# MAXREFDES98_Schematic.net
KiCad netlist of a schematic drawn in EAGLE
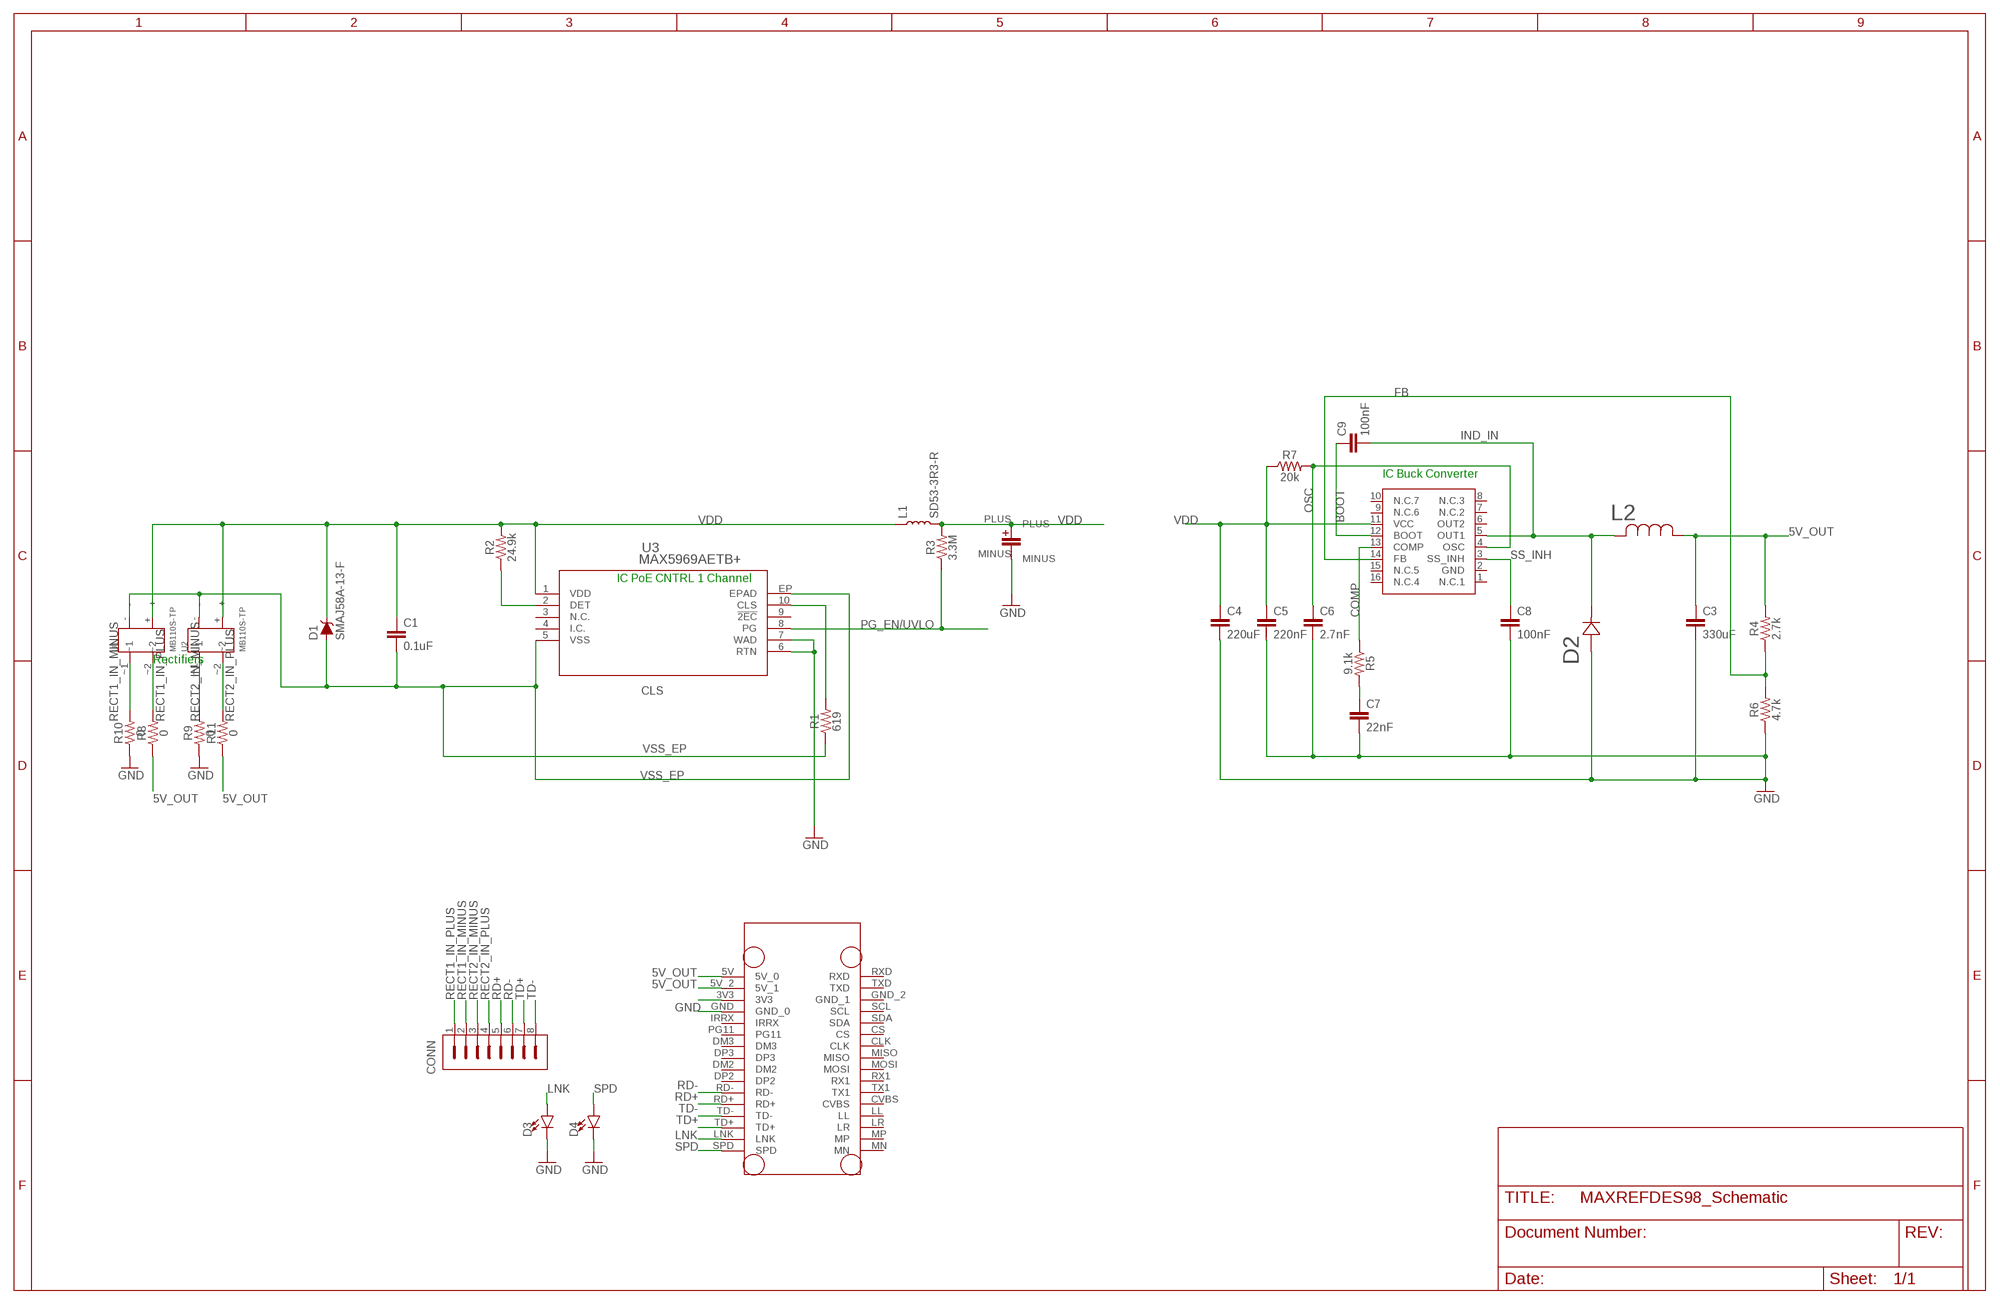
[diagram p0: schematic, sheet 1]

(export (version "E")
  (design (tool "Eeschema 10.0.6"))
  (components
    (comp (ref "C1")
      (value "0.1uF")
      (footprint "eagle-import:0805")
      (libsource (lib "eagle-import") (part "1.0UF-0805-25V-(+80/-20%)"))
    )
    (comp (ref "C2")
      (value "EEE-1JA220UP")
      (footprint "eagle-import:EEE-1JA220UP")
      (libsource (lib "eagle-import") (part "EEE-1JA220UP"))
    )
    (comp (ref "C3")
      (value "330uF")
      (footprint "eagle-import:0603")
      (libsource (lib "eagle-import") (part "4.7UF0603"))
    )
    (comp (ref "C4")
      (value "220uF")
      (footprint "eagle-import:0603")
      (libsource (lib "eagle-import") (part "4.7UF0603"))
    )
    (comp (ref "C5")
      (value "220nF")
      (footprint "eagle-import:0603")
      (libsource (lib "eagle-import") (part "4.7UF0603"))
    )
    (comp (ref "C6")
      (value "2.7nF")
      (footprint "eagle-import:0603")
      (libsource (lib "eagle-import") (part "4.7UF0603"))
    )
    (comp (ref "C7")
      (value "22nF")
      (footprint "eagle-import:0603")
      (libsource (lib "eagle-import") (part "4.7UF0603"))
    )
    (comp (ref "C8")
      (value "100nF")
      (footprint "eagle-import:0603")
      (libsource (lib "eagle-import") (part "4.7UF0603"))
    )
    (comp (ref "C9")
      (value "100nF")
      (footprint "eagle-import:0603")
      (libsource (lib "eagle-import") (part "4.7UF0603"))
    )
    (comp (ref "CONN")
      (value "TERM_BLOCK_PLUG_8POS_STR_2.5MM")
      (footprint "eagle-import:TERM_BLOCK_PLUG_8POS_STR_2.5MM")
      (libsource (lib "eagle-import") (part "TERM_BLOCK_PLUG_8POS_STR_2.5MM"))
    )
    (comp (ref "D1")
      (value "SMAJ58A-13-F")
      (footprint "eagle-import:SMAJ58A-13-F")
      (libsource (lib "eagle-import") (part "SMAJ58A-13-F"))
    )
    (comp (ref "D2")
      (value "STPS3L60USMB_STM-M")
      (footprint "eagle-import:SMB_STM-M")
      (fields (field (name "MANUFACTURER_PART_NUMBER") "STPS3L60U"))
      (libsource (lib "eagle-import") (part "STPS3L60USMB_STM-M"))
    )
    (comp (ref "D3")
      (value "LED-FKIT-1206")
      (footprint "eagle-import:FKIT-LED-1206")
      (libsource (lib "eagle-import") (part "LED-FKIT-1206"))
    )
    (comp (ref "D4")
      (value "LED-FKIT-1206")
      (footprint "eagle-import:FKIT-LED-1206")
      (libsource (lib "eagle-import") (part "LED-FKIT-1206"))
    )
    (comp (ref "L1")
      (value "SD53-3R3-R")
      (footprint "eagle-import:SD53-3R3-R")
      (libsource (lib "eagle-import") (part "SD53-3R3-R"))
    )
    (comp (ref "L2")
      (value "SRR1806-151M")
      (footprint "eagle-import:IND_BOURNS_SRR1806")
      (libsource (lib "eagle-import") (part "SRR1806-151M"))
    )
    (comp (ref "R1")
      (value "619")
      (footprint "eagle-import:0603")
      (libsource (lib "eagle-import") (part "0.05OHM-0603-1/5W-1%"))
    )
    (comp (ref "R2")
      (value "24.9k")
      (footprint "eagle-import:0603")
      (libsource (lib "eagle-import") (part "0.05OHM-0603-1/5W-1%"))
    )
    (comp (ref "R3")
      (value "3.3M")
      (footprint "eagle-import:0603")
      (libsource (lib "eagle-import") (part "0.05OHM-0603-1/5W-1%"))
    )
    (comp (ref "R4")
      (value "2.7k")
      (footprint "eagle-import:0805")
      (libsource (lib "eagle-import") (part "0.22OHM-0805-1/4W-1%"))
    )
    (comp (ref "R5")
      (value "9.1k")
      (footprint "eagle-import:0805")
      (libsource (lib "eagle-import") (part "0.22OHM-0805-1/4W-1%"))
    )
    (comp (ref "R6")
      (value "4.7k")
      (footprint "eagle-import:0805")
      (libsource (lib "eagle-import") (part "0.22OHM-0805-1/4W-1%"))
    )
    (comp (ref "R7")
      (value "20k")
      (footprint "eagle-import:0805")
      (libsource (lib "eagle-import") (part "0.22OHM-0805-1/4W-1%"))
    )
    (comp (ref "R8")
      (value "0")
      (footprint "eagle-import:0603")
      (libsource (lib "eagle-import") (part "0OHM-0603-1/10W-5%"))
    )
    (comp (ref "R9")
      (value "0")
      (footprint "eagle-import:0603")
      (libsource (lib "eagle-import") (part "0OHM-0603-1/10W-5%"))
    )
    (comp (ref "R10")
      (value "0")
      (footprint "eagle-import:0603")
      (libsource (lib "eagle-import") (part "0OHM-0603-1/10W-5%"))
    )
    (comp (ref "R11")
      (value "0")
      (footprint "eagle-import:0603")
      (libsource (lib "eagle-import") (part "0OHM-0603-1/10W-5%"))
    )
    (comp (ref "U$1")
      (value "L4978D013TR")
      (footprint "eagle-import:L4978D013TR")
      (libsource (lib "eagle-import") (part "L4978D013TR"))
    )
    (comp (ref "U$2")
      (value "NANO_PI")
      (footprint "eagle-import:NANO_PI")
      (libsource (lib "eagle-import") (part "NANO_PI"))
    )
    (comp (ref "U1")
      (value "MB110S-TP")
      (footprint "eagle-import:MB110S-TP")
      (libsource (lib "eagle-import") (part "MB110S-TP"))
    )
    (comp (ref "U2")
      (value "MB110S-TP")
      (footprint "eagle-import:MB110S-TP")
      (libsource (lib "eagle-import") (part "MB110S-TP"))
    )
    (comp (ref "U3")
      (value "MAX5969AETB+")
      (footprint "eagle-import:MAX5969AETB+")
      (libsource (lib "eagle-import") (part "MAX5969AETB+"))
    )
  )
  (nets
    (net (code "1") (name "/5V_OUT") (class "Default")
      (node (ref "C3") (pin "1") (pinfunction "1_1") (pintype "passive"))
      (node (ref "L2") (pin "1") (pinfunction "1_1") (pintype "passive"))
      (node (ref "R11") (pin "1") (pinfunction "1_1") (pintype "passive"))
      (node (ref "R4") (pin "2") (pinfunction "2_2") (pintype "passive"))
      (node (ref "R8") (pin "1") (pinfunction "1_1") (pintype "passive"))
      (node (ref "U$2") (pin "5V") (pinfunction "5V_0_5V") (pintype "bidirectional"))
      (node (ref "U$2") (pin "5V_2") (pinfunction "5V_1_5V_2") (pintype "bidirectional"))
    )
    (net (code "2") (name "/BOOT") (class "Default")
      (node (ref "C9") (pin "1") (pinfunction "1_1") (pintype "passive"))
      (node (ref "U$1") (pin "12") (pinfunction "BOOT_12") (pintype "bidirectional"))
    )
    (net (code "3") (name "/CLS") (class "Default")
      (node (ref "R1") (pin "2") (pinfunction "2_2") (pintype "passive"))
      (node (ref "U3") (pin "10") (pinfunction "CLS_10") (pintype "input"))
    )
    (net (code "4") (name "/COMP") (class "Default")
      (node (ref "R5") (pin "1") (pinfunction "1_1") (pintype "passive"))
      (node (ref "U$1") (pin "13") (pinfunction "COMP_13") (pintype "bidirectional"))
    )
    (net (code "5") (name "/FB") (class "Default")
      (node (ref "R4") (pin "1") (pinfunction "1_1") (pintype "passive"))
      (node (ref "R6") (pin "2") (pinfunction "2_2") (pintype "passive"))
      (node (ref "U$1") (pin "14") (pinfunction "FB_14") (pintype "bidirectional"))
    )
    (net (code "6") (name "/IND_IN") (class "Default")
      (node (ref "C9") (pin "2") (pinfunction "2_2") (pintype "passive"))
      (node (ref "D2") (pin "1") (pinfunction "1_1") (pintype "passive"))
      (node (ref "L2") (pin "2") (pinfunction "2_2") (pintype "passive"))
      (node (ref "U$1") (pin "5") (pinfunction "OUT1_5") (pintype "bidirectional"))
    )
    (net (code "7") (name "/LNK") (class "Default")
      (node (ref "D3") (pin "A") (pinfunction "A_A") (pintype "passive"))
      (node (ref "U$2") (pin "LNK") (pinfunction "LNK_LNK") (pintype "bidirectional"))
    )
    (net (code "8") (name "/OSC") (class "Default")
      (node (ref "C6") (pin "1") (pinfunction "1_1") (pintype "passive"))
      (node (ref "R7") (pin "2") (pinfunction "2_2") (pintype "passive"))
      (node (ref "U$1") (pin "4") (pinfunction "OSC_4") (pintype "bidirectional"))
    )
    (net (code "9") (name "/PG_EN{slash}UVLO") (class "Default")
      (node (ref "R3") (pin "1") (pinfunction "1_1") (pintype "passive"))
      (node (ref "U3") (pin "8") (pinfunction "PG_8") (pintype "output"))
    )
    (net (code "10") (name "/RD+") (class "Default")
      (node (ref "CONN") (pin "5") (pinfunction "5_5") (pintype "passive"))
      (node (ref "U$2") (pin "RD+") (pinfunction "RD+_RD+") (pintype "bidirectional"))
    )
    (net (code "11") (name "/RD-") (class "Default")
      (node (ref "CONN") (pin "6") (pinfunction "6_6") (pintype "passive"))
      (node (ref "U$2") (pin "RD-") (pinfunction "RD-_RD-") (pintype "bidirectional"))
    )
    (net (code "12") (name "/RECT1_IN_MINUS") (class "Default")
      (node (ref "CONN") (pin "2") (pinfunction "2_2") (pintype "passive"))
      (node (ref "R10") (pin "2") (pinfunction "2_2") (pintype "passive"))
      (node (ref "U1") (pin "~1") (pinfunction "~{1}_~1") (pintype "bidirectional"))
    )
    (net (code "13") (name "/RECT1_IN_PLUS") (class "Default")
      (node (ref "CONN") (pin "1") (pinfunction "1_1") (pintype "passive"))
      (node (ref "R8") (pin "2") (pinfunction "2_2") (pintype "passive"))
      (node (ref "U1") (pin "~2") (pinfunction "~{2}_~2") (pintype "bidirectional"))
    )
    (net (code "14") (name "/RECT2_IN_MINUS") (class "Default")
      (node (ref "CONN") (pin "3") (pinfunction "3_3") (pintype "passive"))
      (node (ref "R9") (pin "2") (pinfunction "2_2") (pintype "passive"))
      (node (ref "U2") (pin "~1") (pinfunction "~{1}_~1") (pintype "bidirectional"))
    )
    (net (code "15") (name "/RECT2_IN_PLUS") (class "Default")
      (node (ref "CONN") (pin "4") (pinfunction "4_4") (pintype "passive"))
      (node (ref "R11") (pin "2") (pinfunction "2_2") (pintype "passive"))
      (node (ref "U2") (pin "~2") (pinfunction "~{2}_~2") (pintype "bidirectional"))
    )
    (net (code "16") (name "/SPD") (class "Default")
      (node (ref "D4") (pin "A") (pinfunction "A_A") (pintype "passive"))
      (node (ref "U$2") (pin "SPD") (pinfunction "SPD_SPD") (pintype "bidirectional"))
    )
    (net (code "17") (name "/SS_INH") (class "Default")
      (node (ref "C8") (pin "1") (pinfunction "1_1") (pintype "passive"))
      (node (ref "U$1") (pin "3") (pinfunction "SS_INH_3") (pintype "bidirectional"))
    )
    (net (code "18") (name "/TD+") (class "Default")
      (node (ref "CONN") (pin "7") (pinfunction "7_7") (pintype "passive"))
      (node (ref "U$2") (pin "TD+") (pinfunction "TD+_TD+") (pintype "bidirectional"))
    )
    (net (code "19") (name "/TD-") (class "Default")
      (node (ref "CONN") (pin "8") (pinfunction "8_8") (pintype "passive"))
      (node (ref "U$2") (pin "TD-") (pinfunction "TD-_TD-") (pintype "bidirectional"))
    )
    (net (code "20") (name "/VDD") (class "Default")
      (node (ref "C1") (pin "1") (pinfunction "1_1") (pintype "passive"))
      (node (ref "C2") (pin "PLUS") (pinfunction "PLUS_PLUS") (pintype "bidirectional"))
      (node (ref "C4") (pin "1") (pinfunction "1_1") (pintype "passive"))
      (node (ref "C5") (pin "1") (pinfunction "1_1") (pintype "passive"))
      (node (ref "D1") (pin "P$1") (pinfunction "1_P$1") (pintype "passive"))
      (node (ref "L1") (pin "P$1") (pinfunction "1_P$1") (pintype "passive"))
      (node (ref "L1") (pin "P$2") (pinfunction "2_P$2") (pintype "passive"))
      (node (ref "R2") (pin "2") (pinfunction "2_2") (pintype "passive"))
      (node (ref "R3") (pin "2") (pinfunction "2_2") (pintype "passive"))
      (node (ref "R7") (pin "1") (pinfunction "1_1") (pintype "passive"))
      (node (ref "U$1") (pin "11") (pinfunction "VCC_11") (pintype "bidirectional"))
      (node (ref "U1") (pin "+") (pinfunction "+_+") (pintype "bidirectional"))
      (node (ref "U2") (pin "+") (pinfunction "+_+") (pintype "bidirectional"))
      (node (ref "U3") (pin "1") (pinfunction "VDD_1") (pintype "power_in"))
    )
    (net (code "21") (name "/VSS_EP") (class "Default")
      (node (ref "C1") (pin "2") (pinfunction "2_2") (pintype "passive"))
      (node (ref "D1") (pin "P$2") (pinfunction "2_P$2") (pintype "passive"))
      (node (ref "R1") (pin "1") (pinfunction "1_1") (pintype "passive"))
      (node (ref "U1") (pin "-") (pinfunction "-_-") (pintype "bidirectional"))
      (node (ref "U2") (pin "-") (pinfunction "-_-") (pintype "bidirectional"))
      (node (ref "U3") (pin "5") (pinfunction "VSS_5") (pintype "power_in"))
      (node (ref "U3") (pin "EP") (pinfunction "EPAD_EP") (pintype "passive"))
    )
    (net (code "22") (name "GND") (class "Default")
      (node (ref "C2") (pin "MINUS") (pinfunction "MINUS_MINUS") (pintype "bidirectional"))
      (node (ref "C3") (pin "2") (pinfunction "2_2") (pintype "passive"))
      (node (ref "C4") (pin "2") (pinfunction "2_2") (pintype "passive"))
      (node (ref "C5") (pin "2") (pinfunction "2_2") (pintype "passive"))
      (node (ref "C6") (pin "2") (pinfunction "2_2") (pintype "passive"))
      (node (ref "C7") (pin "2") (pinfunction "2_2") (pintype "passive"))
      (node (ref "C8") (pin "2") (pinfunction "2_2") (pintype "passive"))
      (node (ref "D2") (pin "2") (pinfunction "2_2") (pintype "passive"))
      (node (ref "D3") (pin "C") (pinfunction "C_C") (pintype "passive"))
      (node (ref "D4") (pin "C") (pinfunction "C_C") (pintype "passive"))
      (node (ref "R10") (pin "1") (pinfunction "1_1") (pintype "passive"))
      (node (ref "R6") (pin "1") (pinfunction "1_1") (pintype "passive"))
      (node (ref "R9") (pin "1") (pinfunction "1_1") (pintype "passive"))
      (node (ref "U$2") (pin "GND") (pinfunction "GND_0_GND") (pintype "bidirectional"))
      (node (ref "U3") (pin "6") (pinfunction "RTN_6") (pintype "passive"))
      (node (ref "U3") (pin "7") (pinfunction "WAD_7") (pintype "input"))
    )
    (net (code "23") (name "Net-(C7-Pad1)") (class "Default")
      (node (ref "C7") (pin "1") (pinfunction "1_1") (pintype "passive"))
      (node (ref "R5") (pin "2") (pinfunction "2_2") (pintype "passive"))
    )
    (net (code "24") (name "Net-(U3-DET)") (class "Default")
      (node (ref "R2") (pin "1") (pinfunction "1_1") (pintype "passive"))
      (node (ref "U3") (pin "2") (pinfunction "DET_2") (pintype "input"))
    )
    (net (code "25") (name "unconnected-(U$1-GND-Pad2)") (class "Default")
      (node (ref "U$1") (pin "2") (pinfunction "GND_2") (pintype "bidirectional"))
    )
    (net (code "26") (name "unconnected-(U$1-N.C.1-Pad1)") (class "Default")
      (node (ref "U$1") (pin "1") (pinfunction "N.C.1_1") (pintype "bidirectional"))
    )
    (net (code "27") (name "unconnected-(U$1-N.C.2-Pad7)") (class "Default")
      (node (ref "U$1") (pin "7") (pinfunction "N.C.2_7") (pintype "bidirectional"))
    )
    (net (code "28") (name "unconnected-(U$1-N.C.3-Pad8)") (class "Default")
      (node (ref "U$1") (pin "8") (pinfunction "N.C.3_8") (pintype "bidirectional"))
    )
    (net (code "29") (name "unconnected-(U$1-N.C.4-Pad16)") (class "Default")
      (node (ref "U$1") (pin "16") (pinfunction "N.C.4_16") (pintype "bidirectional"))
    )
    (net (code "30") (name "unconnected-(U$1-N.C.5-Pad15)") (class "Default")
      (node (ref "U$1") (pin "15") (pinfunction "N.C.5_15") (pintype "bidirectional"))
    )
    (net (code "31") (name "unconnected-(U$1-N.C.6-Pad9)") (class "Default")
      (node (ref "U$1") (pin "9") (pinfunction "N.C.6_9") (pintype "bidirectional"))
    )
    (net (code "32") (name "unconnected-(U$1-N.C.7-Pad10)") (class "Default")
      (node (ref "U$1") (pin "10") (pinfunction "N.C.7_10") (pintype "bidirectional"))
    )
    (net (code "33") (name "unconnected-(U$1-OUT2-Pad6)") (class "Default")
      (node (ref "U$1") (pin "6") (pinfunction "OUT2_6") (pintype "bidirectional"))
    )
    (net (code "34") (name "unconnected-(U$2-GND_1-PadGND_2)") (class "Default")
      (node (ref "U$2") (pin "GND_2") (pinfunction "GND_1_GND_2") (pintype "bidirectional"))
    )
    (net (code "35") (name "unconnected-(U$2-Pad3V3)") (class "Default")
      (node (ref "U$2") (pin "3V3") (pinfunction "3V3_3V3") (pintype "bidirectional"))
    )
    (net (code "36") (name "unconnected-(U$2-PadCLK)") (class "Default")
      (node (ref "U$2") (pin "CLK") (pinfunction "CLK_CLK") (pintype "bidirectional"))
    )
    (net (code "37") (name "unconnected-(U$2-PadCS)") (class "Default")
      (node (ref "U$2") (pin "CS") (pinfunction "CS_CS") (pintype "bidirectional"))
    )
    (net (code "38") (name "unconnected-(U$2-PadCVBS)") (class "Default")
      (node (ref "U$2") (pin "CVBS") (pinfunction "CVBS_CVBS") (pintype "bidirectional"))
    )
    (net (code "39") (name "unconnected-(U$2-PadDM2)") (class "Default")
      (node (ref "U$2") (pin "DM2") (pinfunction "DM2_DM2") (pintype "bidirectional"))
    )
    (net (code "40") (name "unconnected-(U$2-PadDM3)") (class "Default")
      (node (ref "U$2") (pin "DM3") (pinfunction "DM3_DM3") (pintype "bidirectional"))
    )
    (net (code "41") (name "unconnected-(U$2-PadDP2)") (class "Default")
      (node (ref "U$2") (pin "DP2") (pinfunction "DP2_DP2") (pintype "bidirectional"))
    )
    (net (code "42") (name "unconnected-(U$2-PadDP3)") (class "Default")
      (node (ref "U$2") (pin "DP3") (pinfunction "DP3_DP3") (pintype "bidirectional"))
    )
    (net (code "43") (name "unconnected-(U$2-PadIRRX)") (class "Default")
      (node (ref "U$2") (pin "IRRX") (pinfunction "IRRX_IRRX") (pintype "bidirectional"))
    )
    (net (code "44") (name "unconnected-(U$2-PadLL)") (class "Default")
      (node (ref "U$2") (pin "LL") (pinfunction "LL_LL") (pintype "bidirectional"))
    )
    (net (code "45") (name "unconnected-(U$2-PadLR)") (class "Default")
      (node (ref "U$2") (pin "LR") (pinfunction "LR_LR") (pintype "bidirectional"))
    )
    (net (code "46") (name "unconnected-(U$2-PadMISO)") (class "Default")
      (node (ref "U$2") (pin "MISO") (pinfunction "MISO_MISO") (pintype "bidirectional"))
    )
    (net (code "47") (name "unconnected-(U$2-PadMN)") (class "Default")
      (node (ref "U$2") (pin "MN") (pinfunction "MN_MN") (pintype "bidirectional"))
    )
    (net (code "48") (name "unconnected-(U$2-PadMOSI)") (class "Default")
      (node (ref "U$2") (pin "MOSI") (pinfunction "MOSI_MOSI") (pintype "bidirectional"))
    )
    (net (code "49") (name "unconnected-(U$2-PadMP)") (class "Default")
      (node (ref "U$2") (pin "MP") (pinfunction "MP_MP") (pintype "bidirectional"))
    )
    (net (code "50") (name "unconnected-(U$2-PadPG11)") (class "Default")
      (node (ref "U$2") (pin "PG11") (pinfunction "PG11_PG11") (pintype "bidirectional"))
    )
    (net (code "51") (name "unconnected-(U$2-PadRX1)") (class "Default")
      (node (ref "U$2") (pin "RX1") (pinfunction "RX1_RX1") (pintype "bidirectional"))
    )
    (net (code "52") (name "unconnected-(U$2-PadRXD)") (class "Default")
      (node (ref "U$2") (pin "RXD") (pinfunction "RXD_RXD") (pintype "bidirectional"))
    )
    (net (code "53") (name "unconnected-(U$2-PadSCL)") (class "Default")
      (node (ref "U$2") (pin "SCL") (pinfunction "SCL_SCL") (pintype "bidirectional"))
    )
    (net (code "54") (name "unconnected-(U$2-PadSDA)") (class "Default")
      (node (ref "U$2") (pin "SDA") (pinfunction "SDA_SDA") (pintype "bidirectional"))
    )
    (net (code "55") (name "unconnected-(U$2-PadTX1)") (class "Default")
      (node (ref "U$2") (pin "TX1") (pinfunction "TX1_TX1") (pintype "bidirectional"))
    )
    (net (code "56") (name "unconnected-(U$2-PadTXD)") (class "Default")
      (node (ref "U$2") (pin "TXD") (pinfunction "TXD_TXD") (pintype "bidirectional"))
    )
    (net (code "57") (name "unconnected-(U3-I.C.-Pad4)") (class "Default")
      (node (ref "U3") (pin "4") (pinfunction "I.C._4") (pintype "passive"))
    )
    (net (code "58") (name "unconnected-(U3-N.C.-Pad3)") (class "Default")
      (node (ref "U3") (pin "3") (pinfunction "N.C._3") (pintype "no_connect"))
    )
    (net (code "59") (name "unconnected-(U3-~{2EC}-Pad9)") (class "Default")
      (node (ref "U3") (pin "9") (pinfunction "~{2EC}_9") (pintype "output"))
    )
  )
)
